# T_STorM32_motor_v251E-jst.net
KiCad netlist of a schematic drawn in EAGLE
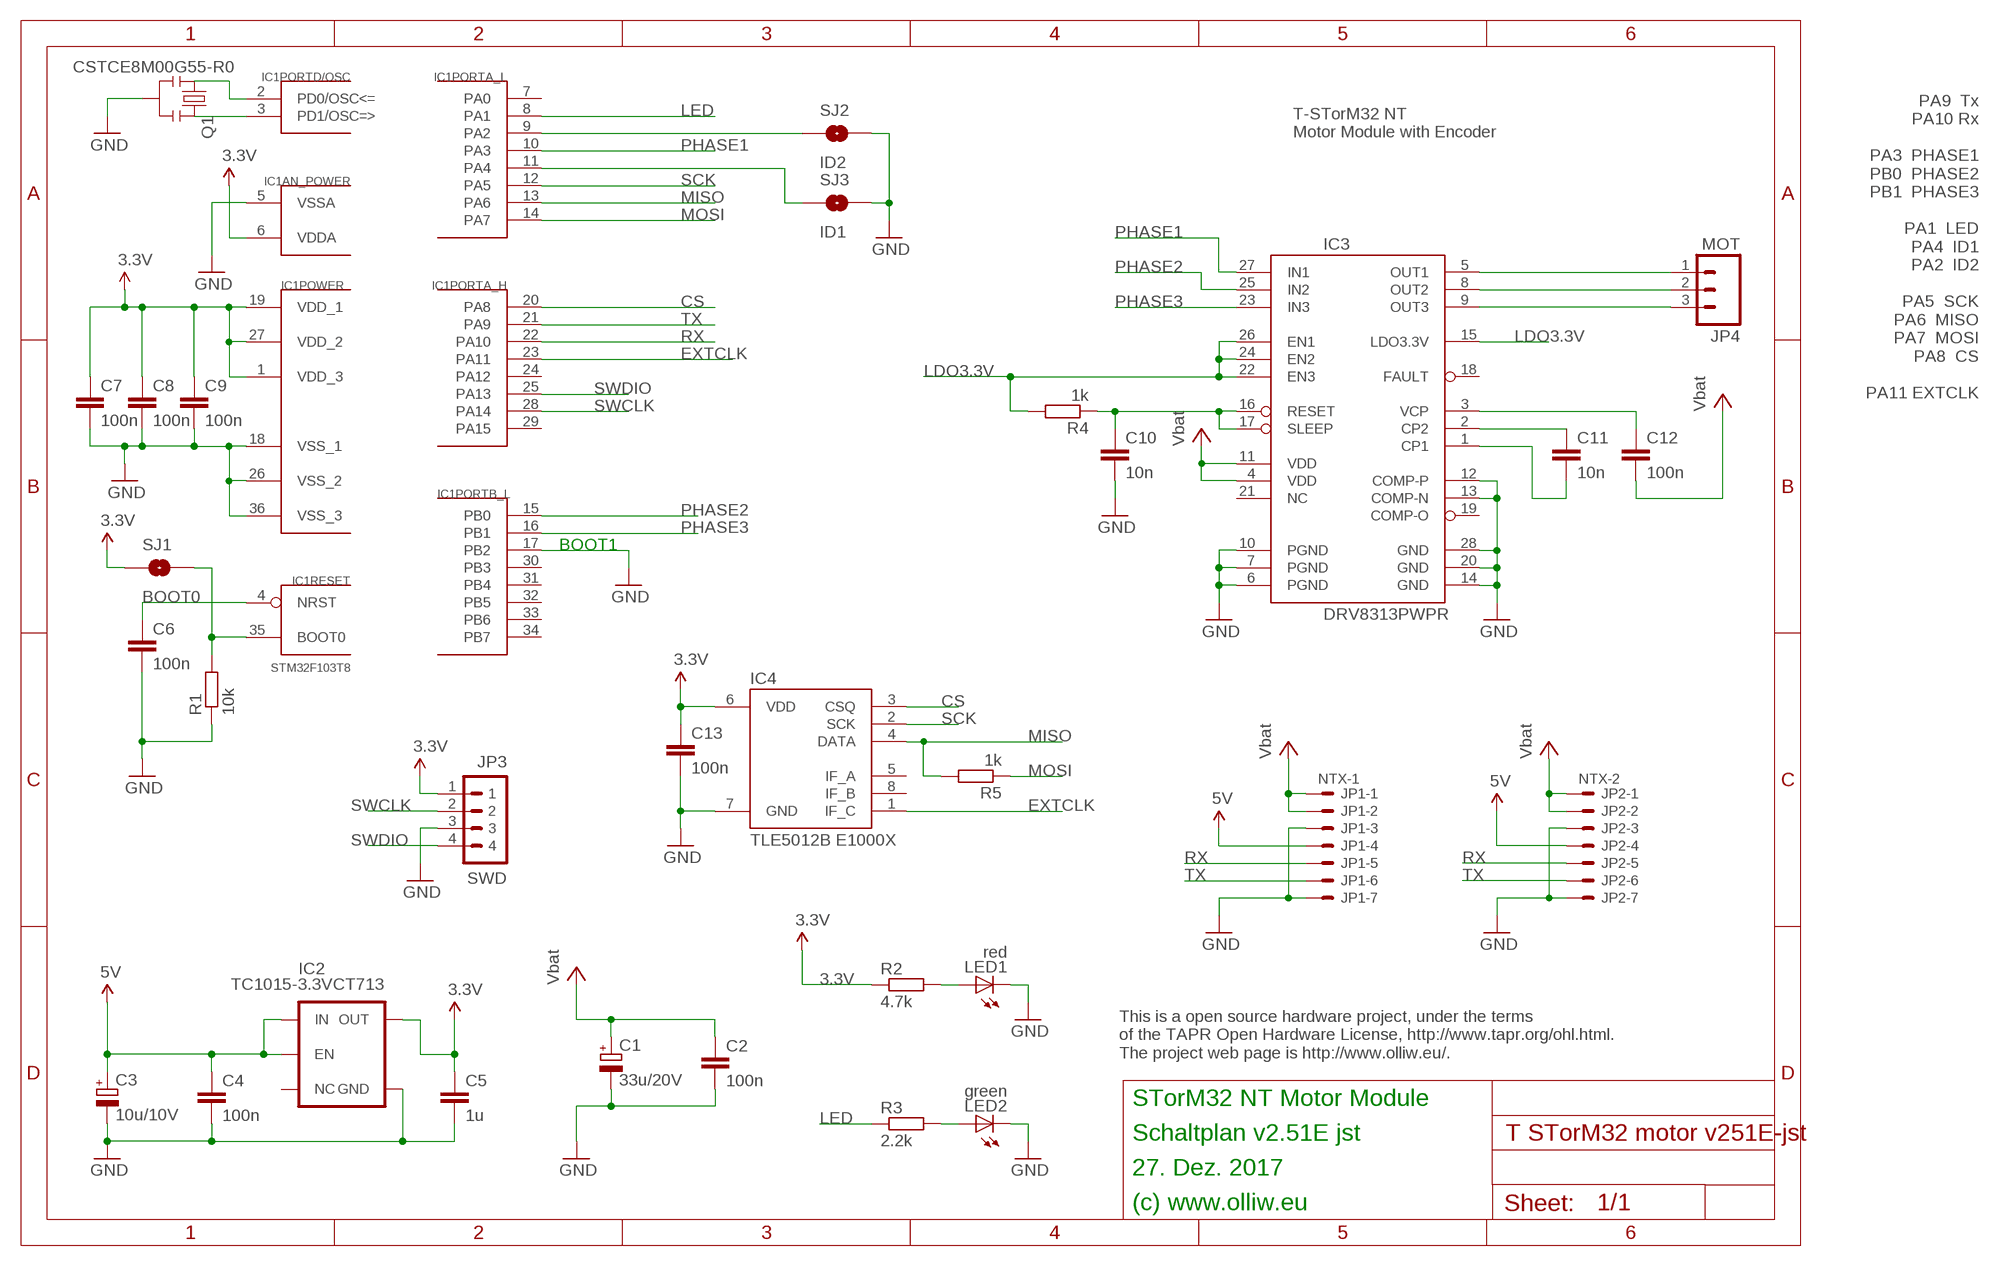
[diagram p0: schematic, sheet 1]

(export (version "E")
  (design (tool "Eeschema 10.0.6"))
  (components
    (comp (ref "C1")
      (value "33u/20V")
      (footprint "eagle-import:SMC_C")
      (libsource (lib "eagle-import") (part "CPOL-EUSMCC"))
    )
    (comp (ref "C2")
      (value "100n")
      (footprint "eagle-import:C0603")
      (libsource (lib "eagle-import") (part "C-EUC0603"))
    )
    (comp (ref "C3")
      (value "10u/10V")
      (footprint "eagle-import:SMC_B")
      (libsource (lib "eagle-import") (part "CPOL-EUSMCB"))
    )
    (comp (ref "C4")
      (value "100n")
      (footprint "eagle-import:C0603")
      (libsource (lib "eagle-import") (part "C-EUC0603"))
    )
    (comp (ref "C5")
      (value "1u")
      (footprint "eagle-import:C0603")
      (libsource (lib "eagle-import") (part "C-EUC0603"))
    )
    (comp (ref "C6")
      (value "100n")
      (footprint "eagle-import:C0603")
      (libsource (lib "eagle-import") (part "C-EUC0603"))
    )
    (comp (ref "C7")
      (value "100n")
      (footprint "eagle-import:C0603")
      (libsource (lib "eagle-import") (part "C-EUC0603"))
    )
    (comp (ref "C8")
      (value "100n")
      (footprint "eagle-import:C0603")
      (libsource (lib "eagle-import") (part "C-EUC0603"))
    )
    (comp (ref "C9")
      (value "100n")
      (footprint "eagle-import:C0603")
      (libsource (lib "eagle-import") (part "C-EUC0603"))
    )
    (comp (ref "C10")
      (value "10n")
      (footprint "eagle-import:C0603")
      (libsource (lib "eagle-import") (part "C-EUC0603"))
    )
    (comp (ref "C11")
      (value "10n")
      (footprint "eagle-import:C0603")
      (libsource (lib "eagle-import") (part "C-EUC0603"))
    )
    (comp (ref "C12")
      (value "100n")
      (footprint "eagle-import:C0603")
      (libsource (lib "eagle-import") (part "C-EUC0603"))
    )
    (comp (ref "C13")
      (value "100n")
      (footprint "eagle-import:C0603")
      (libsource (lib "eagle-import") (part "C-EUC0603"))
    )
    (comp (ref "IC1")
      (value "STM32F103T8")
      (footprint "eagle-import:VFQFPN36")
      (libsource (lib "eagle-import") (part "STM32F10XTXU6"))
    )
    (comp (ref "IC2")
      (value "TC1015-3.3VCT713")
      (footprint "eagle-import:SOT23-5")
      (libsource (lib "eagle-import") (part "V_REG_TPS76433SOT23-5"))
    )
    (comp (ref "IC3")
      (value "DRV8313PWPR")
      (footprint "eagle-import:HTSSOP28")
      (libsource (lib "eagle-import") (part "DRV8313"))
    )
    (comp (ref "IC4")
      (value "TLE5012B E1000X")
      (footprint "eagle-import:SO08")
      (libsource (lib "eagle-import") (part "TLE5012B"))
    )
    (comp (ref "JP1")
      (value "NTX-1")
      (footprint "eagle-import:SM07B-SRSS-TB")
      (libsource (lib "eagle-import") (part "?M07B-SRSS-TBS"))
    )
    (comp (ref "JP2")
      (value "NTX-2")
      (footprint "eagle-import:SM07B-SRSS-TB")
      (libsource (lib "eagle-import") (part "?M07B-SRSS-TBS"))
    )
    (comp (ref "JP3")
      (value "SWD")
      (footprint "eagle-import:4X1_1P27_OCT_BILEX")
      (libsource (lib "eagle-import") (part "P4X1_1P27-OCT_BILEX"))
    )
    (comp (ref "JP4")
      (value "MOT")
      (footprint "eagle-import:1X03")
      (libsource (lib "eagle-import") (part "M03PTH"))
    )
    (comp (ref "LED1")
      (value "red")
      (footprint "eagle-import:CHIPLED_0603")
      (libsource (lib "eagle-import") (part "LEDCHIPLED_0603"))
    )
    (comp (ref "LED2")
      (value "green")
      (footprint "eagle-import:CHIPLED_0603")
      (libsource (lib "eagle-import") (part "LEDCHIPLED_0603"))
    )
    (comp (ref "Q1")
      (value "CSTCE8M00G55-R0")
      (footprint "eagle-import:RESONATOR-SMD")
      (libsource (lib "eagle-import") (part "RESONATORSMD"))
    )
    (comp (ref "R1")
      (value "10k")
      (footprint "eagle-import:R0603")
      (libsource (lib "eagle-import") (part "R-EU_R0603"))
    )
    (comp (ref "R2")
      (value "4.7k")
      (footprint "eagle-import:R0603")
      (libsource (lib "eagle-import") (part "R-EU_R0603"))
    )
    (comp (ref "R3")
      (value "2.2k")
      (footprint "eagle-import:R0603")
      (libsource (lib "eagle-import") (part "R-EU_R0603"))
    )
    (comp (ref "R4")
      (value "1k")
      (footprint "eagle-import:R0603")
      (libsource (lib "eagle-import") (part "R-EU_R0603"))
    )
    (comp (ref "R5")
      (value "1k")
      (footprint "eagle-import:R0603")
      (libsource (lib "eagle-import") (part "R-EU_R0603"))
    )
    (comp (ref "SJ1")
      (value "BOOT0")
      (footprint "eagle-import:SJ_2S-NO")
      (libsource (lib "eagle-import") (part "SOLDERJUMPERNO"))
    )
    (comp (ref "SJ2")
      (value "ID2")
      (footprint "eagle-import:SJ_2S-NO")
      (libsource (lib "eagle-import") (part "SOLDERJUMPERNO"))
    )
    (comp (ref "SJ3")
      (value "ID1")
      (footprint "eagle-import:SJ_2S-NO")
      (libsource (lib "eagle-import") (part "SOLDERJUMPERNO"))
    )
  )
  (nets
    (net (code "1") (name "/CS") (class "Default")
      (node (ref "IC1") (pin "20") (pinfunction "PA8_20") (pintype "bidirectional"))
      (node (ref "IC4") (pin "3") (pinfunction "CSQ_3") (pintype "input"))
    )
    (net (code "2") (name "/EXTCLK") (class "Default")
      (node (ref "IC1") (pin "23") (pinfunction "PA11_23") (pintype "bidirectional"))
      (node (ref "IC4") (pin "1") (pinfunction "IF_C_1") (pintype "bidirectional"))
    )
    (net (code "3") (name "/LDO3.3V") (class "Default")
      (node (ref "IC3") (pin "15") (pinfunction "LDO3.3V_15") (pintype "output"))
      (node (ref "IC3") (pin "22") (pinfunction "EN3_22") (pintype "input"))
      (node (ref "IC3") (pin "24") (pinfunction "EN2_24") (pintype "input"))
      (node (ref "IC3") (pin "26") (pinfunction "EN1_26") (pintype "input"))
      (node (ref "R4") (pin "2") (pinfunction "2_2") (pintype "passive"))
    )
    (net (code "4") (name "/LED") (class "Default")
      (node (ref "IC1") (pin "8") (pinfunction "PA1_8") (pintype "bidirectional"))
      (node (ref "R3") (pin "1") (pinfunction "1_1") (pintype "passive"))
    )
    (net (code "5") (name "/MISO") (class "Default")
      (node (ref "IC1") (pin "13") (pinfunction "PA6_13") (pintype "bidirectional"))
      (node (ref "IC4") (pin "4") (pinfunction "DATA_4") (pintype "bidirectional"))
      (node (ref "R5") (pin "2") (pinfunction "2_2") (pintype "passive"))
    )
    (net (code "6") (name "/MOSI") (class "Default")
      (node (ref "IC1") (pin "14") (pinfunction "PA7_14") (pintype "bidirectional"))
      (node (ref "R5") (pin "1") (pinfunction "1_1") (pintype "passive"))
    )
    (net (code "7") (name "/PHASE1") (class "Default")
      (node (ref "IC1") (pin "10") (pinfunction "PA3_10") (pintype "bidirectional"))
      (node (ref "IC3") (pin "27") (pinfunction "IN1_27") (pintype "input"))
    )
    (net (code "8") (name "/PHASE2") (class "Default")
      (node (ref "IC1") (pin "15") (pinfunction "PB0_15") (pintype "bidirectional"))
      (node (ref "IC3") (pin "25") (pinfunction "IN2_25") (pintype "input"))
    )
    (net (code "9") (name "/PHASE3") (class "Default")
      (node (ref "IC1") (pin "16") (pinfunction "PB1_16") (pintype "bidirectional"))
      (node (ref "IC3") (pin "23") (pinfunction "IN3_23") (pintype "input"))
    )
    (net (code "10") (name "/RX") (class "Default")
      (node (ref "IC1") (pin "22") (pinfunction "PA10_22") (pintype "bidirectional"))
      (node (ref "JP1") (pin "5") (pinfunction "S_5") (pintype "passive"))
      (node (ref "JP2") (pin "5") (pinfunction "S_5") (pintype "passive"))
    )
    (net (code "11") (name "/SCK") (class "Default")
      (node (ref "IC1") (pin "12") (pinfunction "PA5_12") (pintype "bidirectional"))
      (node (ref "IC4") (pin "2") (pinfunction "SCK_2") (pintype "input"))
    )
    (net (code "12") (name "/SWCLK") (class "Default")
      (node (ref "IC1") (pin "28") (pinfunction "PA14_28") (pintype "bidirectional"))
      (node (ref "JP3") (pin "2") (pinfunction "2_2") (pintype "passive"))
    )
    (net (code "13") (name "/SWDIO") (class "Default")
      (node (ref "IC1") (pin "25") (pinfunction "PA13_25") (pintype "bidirectional"))
      (node (ref "JP3") (pin "4") (pinfunction "4_4") (pintype "passive"))
    )
    (net (code "14") (name "/TX") (class "Default")
      (node (ref "IC1") (pin "21") (pinfunction "PA9_21") (pintype "bidirectional"))
      (node (ref "JP1") (pin "6") (pinfunction "S_6") (pintype "passive"))
      (node (ref "JP2") (pin "6") (pinfunction "S_6") (pintype "passive"))
    )
    (net (code "15") (name "3.3V") (class "Default")
      (node (ref "C13") (pin "1") (pinfunction "1_1") (pintype "passive"))
      (node (ref "C5") (pin "1") (pinfunction "1_1") (pintype "passive"))
      (node (ref "C7") (pin "1") (pinfunction "1_1") (pintype "passive"))
      (node (ref "C8") (pin "1") (pinfunction "1_1") (pintype "passive"))
      (node (ref "C9") (pin "1") (pinfunction "1_1") (pintype "passive"))
      (node (ref "IC1") (pin "1") (pinfunction "VDD_3_1") (pintype "power_in"))
      (node (ref "IC1") (pin "19") (pinfunction "VDD_1_19") (pintype "power_in"))
      (node (ref "IC1") (pin "27") (pinfunction "VDD_2_27") (pintype "power_in"))
      (node (ref "IC1") (pin "6") (pinfunction "VDDA_6") (pintype "power_in"))
      (node (ref "IC2") (pin "5") (pinfunction "OUT_5") (pintype "passive"))
      (node (ref "IC4") (pin "6") (pinfunction "VDD_6") (pintype "power_in"))
      (node (ref "JP3") (pin "1") (pinfunction "1_1") (pintype "passive"))
      (node (ref "R2") (pin "1") (pinfunction "1_1") (pintype "passive"))
      (node (ref "SJ1") (pin "1") (pinfunction "1_1") (pintype "passive"))
    )
    (net (code "16") (name "5V") (class "Default")
      (node (ref "C3") (pin "+") (pinfunction "+_+") (pintype "passive"))
      (node (ref "C4") (pin "1") (pinfunction "1_1") (pintype "passive"))
      (node (ref "IC2") (pin "1") (pinfunction "IN_1") (pintype "input"))
      (node (ref "IC2") (pin "3") (pinfunction "EN_3") (pintype "input"))
      (node (ref "JP1") (pin "4") (pinfunction "S_4") (pintype "passive"))
      (node (ref "JP2") (pin "4") (pinfunction "S_4") (pintype "passive"))
    )
    (net (code "17") (name "GND") (class "Default")
      (node (ref "C1") (pin "-") (pinfunction "-_-") (pintype "passive"))
      (node (ref "C10") (pin "2") (pinfunction "2_2") (pintype "passive"))
      (node (ref "C13") (pin "2") (pinfunction "2_2") (pintype "passive"))
      (node (ref "C2") (pin "2") (pinfunction "2_2") (pintype "passive"))
      (node (ref "C3") (pin "-") (pinfunction "-_-") (pintype "passive"))
      (node (ref "C4") (pin "2") (pinfunction "2_2") (pintype "passive"))
      (node (ref "C5") (pin "2") (pinfunction "2_2") (pintype "passive"))
      (node (ref "C6") (pin "2") (pinfunction "2_2") (pintype "passive"))
      (node (ref "C7") (pin "2") (pinfunction "2_2") (pintype "passive"))
      (node (ref "C8") (pin "2") (pinfunction "2_2") (pintype "passive"))
      (node (ref "C9") (pin "2") (pinfunction "2_2") (pintype "passive"))
      (node (ref "IC1") (pin "17") (pinfunction "PB2_17") (pintype "bidirectional"))
      (node (ref "IC1") (pin "18") (pinfunction "VSS_1_18") (pintype "power_in"))
      (node (ref "IC1") (pin "26") (pinfunction "VSS_2_26") (pintype "power_in"))
      (node (ref "IC1") (pin "36") (pinfunction "VSS_3_36") (pintype "power_in"))
      (node (ref "IC1") (pin "5") (pinfunction "VSSA_5") (pintype "power_in"))
      (node (ref "IC2") (pin "2") (pinfunction "GND_2") (pintype "input"))
      (node (ref "IC3") (pin "10") (pinfunction "PGND_10") (pintype "power_in"))
      (node (ref "IC3") (pin "12") (pinfunction "COMP-P_12") (pintype "input"))
      (node (ref "IC3") (pin "13") (pinfunction "COMP-N_13") (pintype "input"))
      (node (ref "IC3") (pin "14") (pinfunction "GND_14") (pintype "power_in"))
      (node (ref "IC3") (pin "20") (pinfunction "GND_20") (pintype "power_in"))
      (node (ref "IC3") (pin "28") (pinfunction "GND_28") (pintype "power_in"))
      (node (ref "IC3") (pin "6") (pinfunction "PGND_6") (pintype "power_in"))
      (node (ref "IC3") (pin "7") (pinfunction "PGND_7") (pintype "power_in"))
      (node (ref "IC4") (pin "7") (pinfunction "GND_7") (pintype "power_in"))
      (node (ref "JP1") (pin "3") (pinfunction "S_3") (pintype "passive"))
      (node (ref "JP1") (pin "7") (pinfunction "S_7") (pintype "passive"))
      (node (ref "JP2") (pin "3") (pinfunction "S_3") (pintype "passive"))
      (node (ref "JP2") (pin "7") (pinfunction "S_7") (pintype "passive"))
      (node (ref "JP3") (pin "3") (pinfunction "3_3") (pintype "passive"))
      (node (ref "LED1") (pin "C") (pinfunction "C_C") (pintype "passive"))
      (node (ref "LED2") (pin "C") (pinfunction "C_C") (pintype "passive"))
      (node (ref "Q1") (pin "2") (pinfunction "2_2") (pintype "passive"))
      (node (ref "R1") (pin "1") (pinfunction "1_1") (pintype "passive"))
      (node (ref "SJ2") (pin "2") (pinfunction "2_2") (pintype "passive"))
      (node (ref "SJ3") (pin "2") (pinfunction "2_2") (pintype "passive"))
    )
    (net (code "18") (name "Net-(IC1C-PA2)") (class "Default")
      (node (ref "IC1") (pin "9") (pinfunction "PA2_9") (pintype "bidirectional"))
      (node (ref "SJ2") (pin "1") (pinfunction "1_1") (pintype "passive"))
    )
    (net (code "19") (name "Net-(IC1C-PA4)") (class "Default")
      (node (ref "IC1") (pin "11") (pinfunction "PA4_11") (pintype "bidirectional"))
      (node (ref "SJ3") (pin "1") (pinfunction "1_1") (pintype "passive"))
    )
    (net (code "20") (name "Net-(IC1E-PD0{slash}OSC<=)") (class "Default")
      (node (ref "IC1") (pin "2") (pinfunction "PD0/OSC<=_2") (pintype "bidirectional"))
      (node (ref "Q1") (pin "1") (pinfunction "1_1") (pintype "passive"))
    )
    (net (code "21") (name "Net-(IC1E-PD1{slash}OSC=>)") (class "Default")
      (node (ref "IC1") (pin "3") (pinfunction "PD1/OSC=>_3") (pintype "bidirectional"))
      (node (ref "Q1") (pin "3") (pinfunction "3_3") (pintype "passive"))
    )
    (net (code "22") (name "Net-(IC1G-BOOT0)") (class "Default")
      (node (ref "IC1") (pin "35") (pinfunction "BOOT0_35") (pintype "input"))
      (node (ref "R1") (pin "2") (pinfunction "2_2") (pintype "passive"))
      (node (ref "SJ1") (pin "2") (pinfunction "2_2") (pintype "passive"))
    )
    (net (code "23") (name "Net-(IC1G-NRST)") (class "Default")
      (node (ref "C6") (pin "1") (pinfunction "1_1") (pintype "passive"))
      (node (ref "IC1") (pin "4") (pinfunction "NRST_4") (pintype "input"))
    )
    (net (code "24") (name "Net-(IC3-CP1)") (class "Default")
      (node (ref "C11") (pin "2") (pinfunction "2_2") (pintype "passive"))
      (node (ref "IC3") (pin "1") (pinfunction "CP1_1") (pintype "bidirectional"))
    )
    (net (code "25") (name "Net-(IC3-CP2)") (class "Default")
      (node (ref "C11") (pin "1") (pinfunction "1_1") (pintype "passive"))
      (node (ref "IC3") (pin "2") (pinfunction "CP2_2") (pintype "bidirectional"))
    )
    (net (code "26") (name "Net-(IC3-OUT1)") (class "Default")
      (node (ref "IC3") (pin "5") (pinfunction "OUT1_5") (pintype "output"))
      (node (ref "JP4") (pin "1") (pinfunction "1_1") (pintype "passive"))
    )
    (net (code "27") (name "Net-(IC3-OUT2)") (class "Default")
      (node (ref "IC3") (pin "8") (pinfunction "OUT2_8") (pintype "output"))
      (node (ref "JP4") (pin "2") (pinfunction "2_2") (pintype "passive"))
    )
    (net (code "28") (name "Net-(IC3-OUT3)") (class "Default")
      (node (ref "IC3") (pin "9") (pinfunction "OUT3_9") (pintype "output"))
      (node (ref "JP4") (pin "3") (pinfunction "3_3") (pintype "passive"))
    )
    (net (code "29") (name "Net-(IC3-RESET)") (class "Default")
      (node (ref "C10") (pin "1") (pinfunction "1_1") (pintype "passive"))
      (node (ref "IC3") (pin "16") (pinfunction "RESET_16") (pintype "input"))
      (node (ref "IC3") (pin "17") (pinfunction "SLEEP_17") (pintype "input"))
      (node (ref "R4") (pin "1") (pinfunction "1_1") (pintype "passive"))
    )
    (net (code "30") (name "Net-(IC3-VCP)") (class "Default")
      (node (ref "C12") (pin "1") (pinfunction "1_1") (pintype "passive"))
      (node (ref "IC3") (pin "3") (pinfunction "VCP_3") (pintype "bidirectional"))
    )
    (net (code "31") (name "Net-(LED1-PadA)") (class "Default")
      (node (ref "LED1") (pin "A") (pinfunction "A_A") (pintype "passive"))
      (node (ref "R2") (pin "2") (pinfunction "2_2") (pintype "passive"))
    )
    (net (code "32") (name "Net-(LED2-PadA)") (class "Default")
      (node (ref "LED2") (pin "A") (pinfunction "A_A") (pintype "passive"))
      (node (ref "R3") (pin "2") (pinfunction "2_2") (pintype "passive"))
    )
    (net (code "33") (name "Vbat") (class "Default")
      (node (ref "C1") (pin "+") (pinfunction "+_+") (pintype "passive"))
      (node (ref "C12") (pin "2") (pinfunction "2_2") (pintype "passive"))
      (node (ref "C2") (pin "1") (pinfunction "1_1") (pintype "passive"))
      (node (ref "IC3") (pin "11") (pinfunction "VDD_11") (pintype "power_in"))
      (node (ref "IC3") (pin "4") (pinfunction "VDD_4") (pintype "power_in"))
      (node (ref "JP1") (pin "1") (pinfunction "S_1") (pintype "passive"))
      (node (ref "JP1") (pin "2") (pinfunction "S_2") (pintype "passive"))
      (node (ref "JP2") (pin "1") (pinfunction "S_1") (pintype "passive"))
      (node (ref "JP2") (pin "2") (pinfunction "S_2") (pintype "passive"))
    )
    (net (code "34") (name "unconnected-(IC1B-PA12-Pad24)") (class "Default")
      (node (ref "IC1") (pin "24") (pinfunction "PA12_24") (pintype "bidirectional"))
    )
    (net (code "35") (name "unconnected-(IC1B-PA15-Pad29)") (class "Default")
      (node (ref "IC1") (pin "29") (pinfunction "PA15_29") (pintype "bidirectional"))
    )
    (net (code "36") (name "unconnected-(IC1C-PA0-Pad7)") (class "Default")
      (node (ref "IC1") (pin "7") (pinfunction "PA0_7") (pintype "bidirectional"))
    )
    (net (code "37") (name "unconnected-(IC1D-PB3-Pad30)") (class "Default")
      (node (ref "IC1") (pin "30") (pinfunction "PB3_30") (pintype "bidirectional"))
    )
    (net (code "38") (name "unconnected-(IC1D-PB4-Pad31)") (class "Default")
      (node (ref "IC1") (pin "31") (pinfunction "PB4_31") (pintype "bidirectional"))
    )
    (net (code "39") (name "unconnected-(IC1D-PB5-Pad32)") (class "Default")
      (node (ref "IC1") (pin "32") (pinfunction "PB5_32") (pintype "bidirectional"))
    )
    (net (code "40") (name "unconnected-(IC1D-PB6-Pad33)") (class "Default")
      (node (ref "IC1") (pin "33") (pinfunction "PB6_33") (pintype "bidirectional"))
    )
    (net (code "41") (name "unconnected-(IC1D-PB7-Pad34)") (class "Default")
      (node (ref "IC1") (pin "34") (pinfunction "PB7_34") (pintype "bidirectional"))
    )
    (net (code "42") (name "unconnected-(IC2-NC-Pad4)") (class "Default")
      (node (ref "IC2") (pin "4") (pinfunction "NC_4") (pintype "input"))
    )
    (net (code "43") (name "unconnected-(IC3-COMP-O-Pad19)") (class "Default")
      (node (ref "IC3") (pin "19") (pinfunction "COMP-O_19") (pintype "output"))
    )
    (net (code "44") (name "unconnected-(IC3-FAULT-Pad18)") (class "Default")
      (node (ref "IC3") (pin "18") (pinfunction "FAULT_18") (pintype "output"))
    )
    (net (code "45") (name "unconnected-(IC3-NC-Pad21)") (class "Default")
      (node (ref "IC3") (pin "21") (pinfunction "NC_21") (pintype "no_connect"))
    )
    (net (code "46") (name "unconnected-(IC4-IF_A-Pad5)") (class "Default")
      (node (ref "IC4") (pin "5") (pinfunction "IF_A_5") (pintype "bidirectional"))
    )
    (net (code "47") (name "unconnected-(IC4-IF_B-Pad8)") (class "Default")
      (node (ref "IC4") (pin "8") (pinfunction "IF_B_8") (pintype "output"))
    )
  )
)
